# Main.net
KiCad netlist of a schematic drawn in Altium Designer
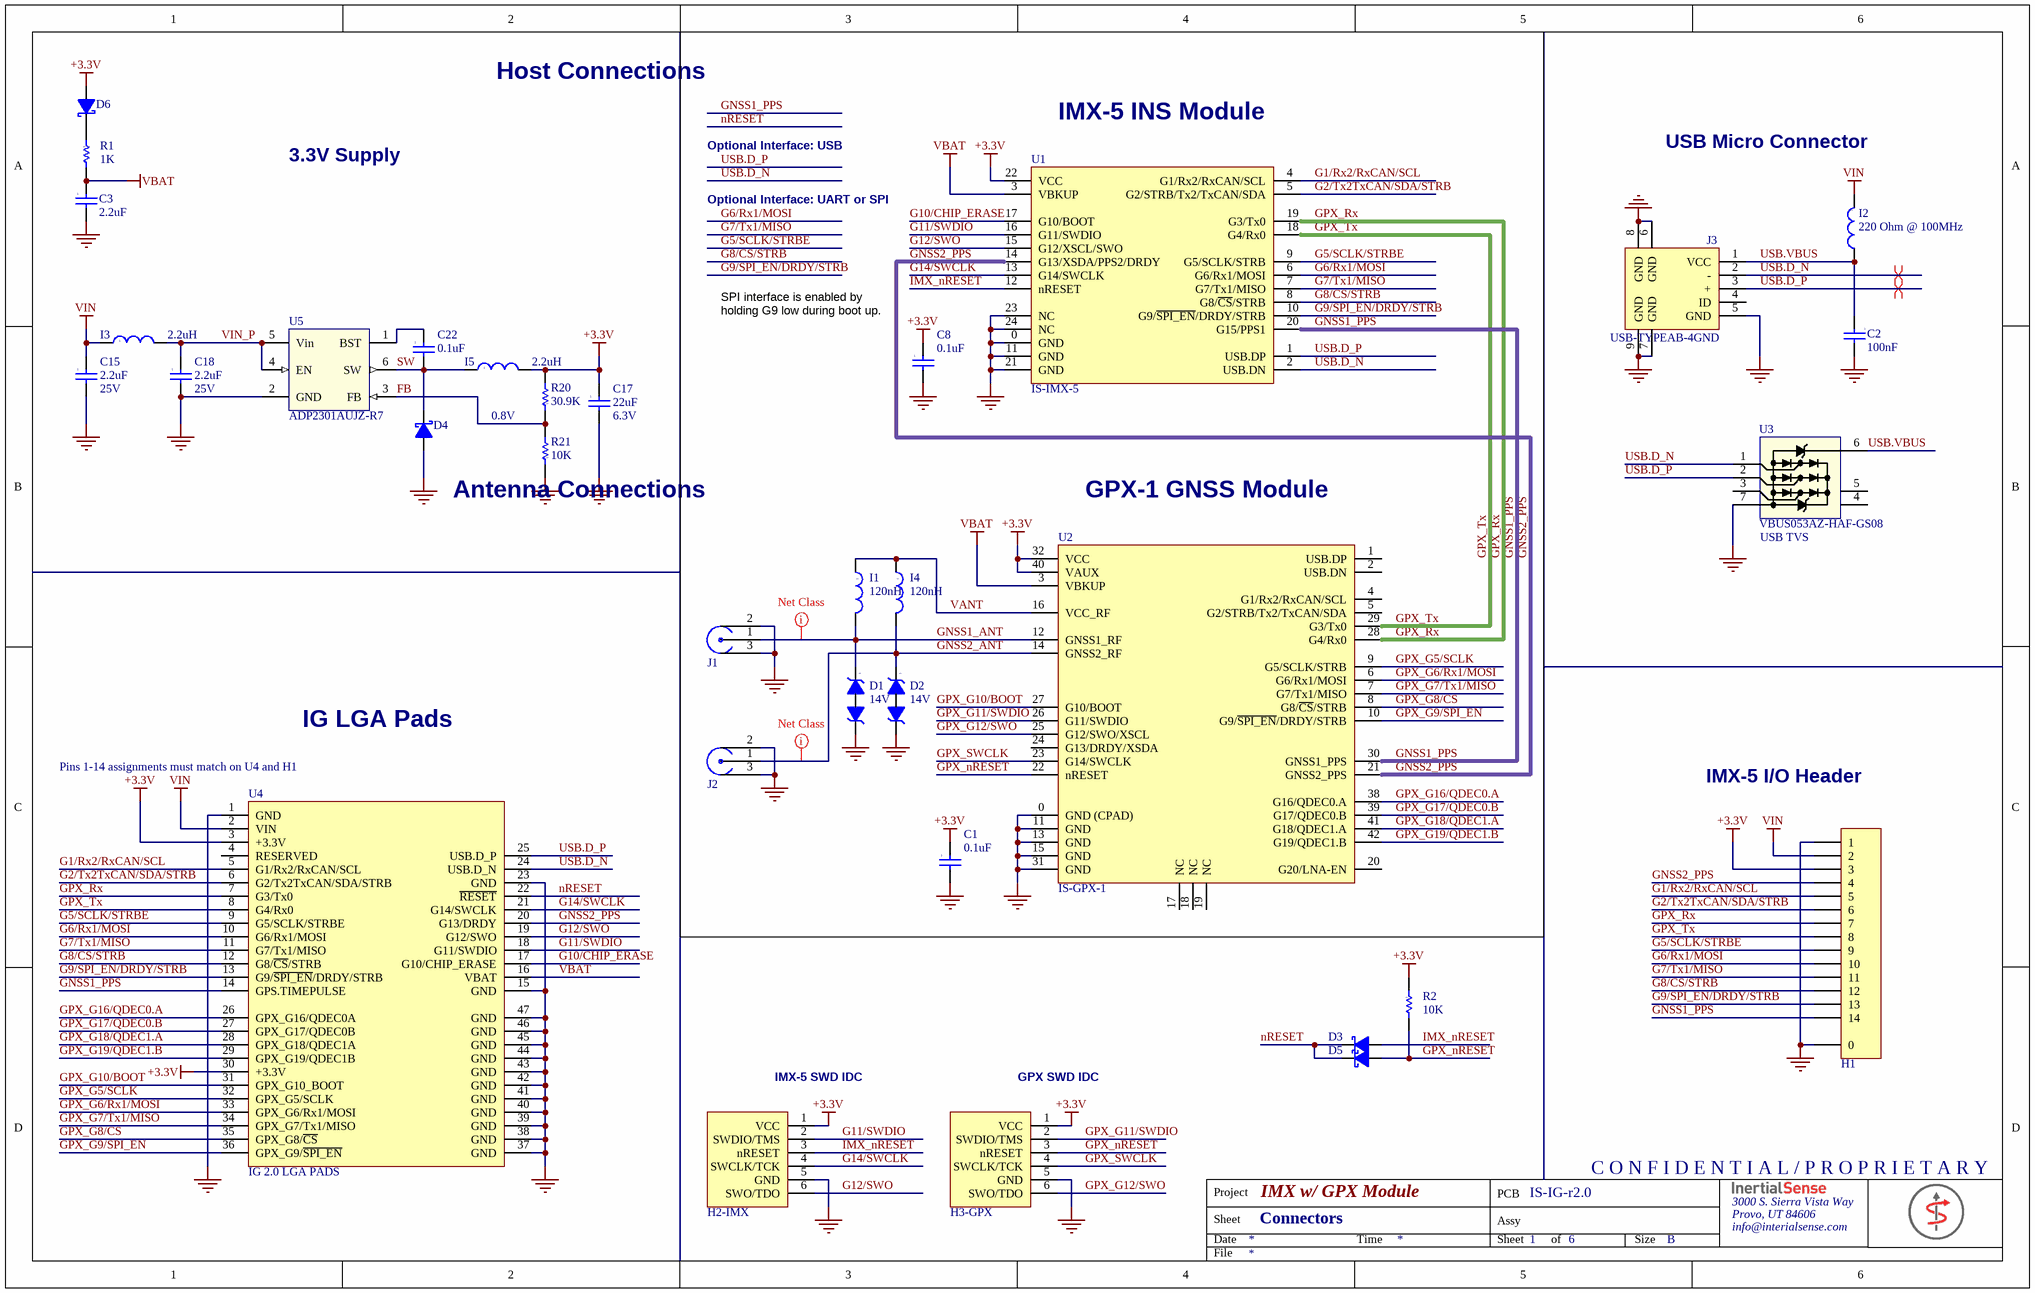
[diagram p0: Main.SchDoc]

(export (version "E")
  (design (tool "Eeschema 10.0.6"))
  (components
    (comp (ref "C1")
      (value "0.1uF")
      (footprint "0402")
      (description "CAP CER .10UF 50V X7R 10% 0402")
      (fields
        (field (name "MANUFACTURER") "TDK Corporation")
        (field (name "MANUFACTURER PART NUMBER") "C1005X7R1H104K")
        (field (name "PUBLISHER") "Altium Limited")
      )
      (libsource (lib "General") (part "Cap"))
    )
    (comp (ref "C2")
      (value "100nF")
      (footprint "0402")
      (description "CAP CER .10UF 50V X7R 10% 0402")
      (fields
        (field (name "MANUFACTURER") "TDK Corporation")
        (field (name "MANUFACTURER PART NUMBER") "C1005X7R1H104K")
        (field (name "PUBLISHER") "Altium Limited")
      )
      (libsource (lib "General") (part "Cap"))
    )
    (comp (ref "C3")
      (value "2.2uF")
      (footprint "0402")
      (description "0402 2.2 uF 6.3 V ±10% Tolerance X6S Multilayer Ceramic Capacitor")
      (fields
        (field (name "MANUFACTURER") "Murata")
        (field (name "MANUFACTURER PART NUMBER") "GRM155C80J225KE95D")
        (field (name "PUBLISHER") "Altium Limited")
      )
      (libsource (lib "General") (part "Cap"))
    )
    (comp (ref "C8")
      (value "0.1uF")
      (footprint "0402")
      (description "CAP CER .10UF 50V X7R 10% 0402")
      (fields
        (field (name "MANUFACTURER") "TDK Corporation")
        (field (name "MANUFACTURER PART NUMBER") "C1005X7R1H104K")
        (field (name "PUBLISHER") "Altium Limited")
      )
      (libsource (lib "General") (part "Cap"))
    )
    (comp (ref "C15")
      (value "2.2uF")
      (footprint "0603")
      (description "CAP CER 2.2UF 25V X6S 0603")
      (fields
        (field (name "MANUFACTURER") "Murata")
        (field (name "MANUFACTURER PART NUMBER") "GRT188C81E225KE13D")
        (field (name "VOLTAGE RATING") "25V")
        (field (name "PUBLISHER") "Altium Limited")
      )
      (libsource (lib "General") (part "Cap"))
    )
    (comp (ref "C17")
      (value "22uF")
      (footprint "0603")
      (description "CAP CER 22UF 6.3V X6S 0603")
      (fields
        (field (name "MANUFACTURER") "Murata")
        (field (name "MANUFACTURER PART NUMBER") "GRM188C80J226ME15D")
        (field (name "VOLTAGE RATING") "6.3V")
        (field (name "PUBLISHER") "Altium Limited")
      )
      (libsource (lib "General") (part "Cap"))
    )
    (comp (ref "C18")
      (value "2.2uF")
      (footprint "0603")
      (description "CAP CER 2.2UF 25V X6S 0603")
      (fields
        (field (name "MANUFACTURER") "Murata")
        (field (name "MANUFACTURER PART NUMBER") "GRT188C81E225KE13D")
        (field (name "VOLTAGE RATING") "25V")
        (field (name "PUBLISHER") "Altium Limited")
      )
      (libsource (lib "General") (part "Cap"))
    )
    (comp (ref "C22")
      (value "0.1uF")
      (footprint "0402")
      (description "CAP CER 0.1UF 50V X7R 0402")
      (fields
        (field (name "MANUFACTURER") "TDK")
        (field (name "MANUFACTURER PART NUMBER") "CGA2B3X7R1H104K050BB")
        (field (name "PUBLISHER") "Altium Limited")
      )
      (libsource (lib "General") (part "Cap"))
    )
    (comp (ref "D1")
      (value "Diode - Bidirectional Zener")
      (footprint "R0402")
      (description "LITTELFUSE - PESD0402-140 - DIODE, ESD PROTECTION, 0402, FULL REEL")
      (fields
        (field (name "MANUFACTURER") "Littelfuse")
        (field (name "MANUFACTURER PART NUMBER") "PESD0402-140")
        (field (name "WORKING VOLTAGE") "14V")
      )
      (libsource (lib "General") (part "Diode - Bidirectional Zener"))
    )
    (comp (ref "D2")
      (value "Diode - Bidirectional Zener")
      (footprint "R0402")
      (description "LITTELFUSE - PESD0402-140 - DIODE, ESD PROTECTION, 0402, FULL REEL")
      (fields
        (field (name "MANUFACTURER") "Littelfuse")
        (field (name "MANUFACTURER PART NUMBER") "PESD0402-140")
        (field (name "WORKING VOLTAGE") "14V")
      )
      (libsource (lib "General") (part "Diode - Bidirectional Zener"))
    )
    (comp (ref "D3")
      (value "Diode - Schottky")
      (footprint "D0402")
      (description "CDBQR0130L; SMT Schottky Diode; 35V 100mA; 2-Pin SOD-923F (0402)")
      (fields (field (name "MANUFACTURER") "Comchip") (field (name "MANUFACTURER PART NUMBER") "CDBQR0130L"))
      (libsource (lib "General") (part "Diode - Schottky"))
    )
    (comp (ref "D4")
      (value "Diode - Schottky")
      (footprint "D0603B")
      (description "DIODE SCHOTTKY 30V 2A 0603")
      (fields
        (field (name "MANUFACTURER") "Vishay")
        (field (name "MANUFACTURER PART NUMBER") "VSKY20301608-G4-08")
      )
      (libsource (lib "General") (part "Diode - Schottky"))
    )
    (comp (ref "D5")
      (value "Diode - Schottky")
      (footprint "D0402")
      (description "CDBQR0130L; SMT Schottky Diode; 35V 100mA; 2-Pin SOD-923F (0402)")
      (fields (field (name "MANUFACTURER") "Comchip") (field (name "MANUFACTURER PART NUMBER") "CDBQR0130L"))
      (libsource (lib "General") (part "Diode - Schottky"))
    )
    (comp (ref "D6")
      (value "Diode - Schottky")
      (footprint "D0603B")
      (description "DIODE SCHOTTKY 30V 2A 0603")
      (fields
        (field (name "MANUFACTURER") "Vishay")
        (field (name "MANUFACTURER PART NUMBER") "VSKY20301608-G4-08")
      )
      (libsource (lib "General") (part "Diode - Schottky"))
    )
    (comp (ref "H1")
      (value "Hdr - 14pin - mount")
      (footprint "SM14B-GHS-TB(LF)(SN)")
      (description "Conn Shrouded Header HDR 14 POS 1.25mm Solder ST Top Entry SMD T/R")
      (fields
        (field (name "MANUFACTURER") "JST")
        (field (name "MANUFACTURER PART NUMBER") "SM14B-GHS-TB(LF)(SN)")
      )
      (libsource (lib "Connectors") (part "Hdr - 14pin - mount"))
    )
    (comp (ref "H2-IMX")
      (value "TC2030-IDC")
      (footprint "TC2030-IDC-NL")
      (description "6 pin header")
      (libsource (lib "Connectors") (part "TC2030-IDC"))
    )
    (comp (ref "H3-GPX")
      (value "TC2030-IDC")
      (footprint "TC2030-IDC-NL")
      (description "6 pin header")
      (libsource (lib "Connectors") (part "TC2030-IDC"))
    )
    (comp (ref "I1")
      (value "120nH")
      (footprint "0402")
      (description "Inductor RF Chip Wirewound 120nH 5% 100MHz 20Q-Factor 110mA 2.66Ohm DCR 0402 Paper T/R")
      (fields
        (field (name "MANUFACTURER") "Murata")
        (field (name "MANUFACTURER PART NUMBER") "LQW15ANR12J00D")
      )
      (libsource (lib "") (part "Inductor_1"))
    )
    (comp (ref "I2")
      (value "220 Ohm @ 100MHz")
      (footprint "I0603")
      (description "FERRITE CHIP 220 OHM 2500MA 0603")
      (fields
        (field (name "MANUFACTURER") "Murata Electronics North America")
        (field (name "MANUFACTURER PART NUMBER") "BLM18SG221TN1D")
      )
      (libsource (lib "General") (part "Inductor"))
    )
    (comp (ref "I3")
      (value "2.2uH")
      (footprint "0806")
      (description "FIXED IND 2.2UH 1.2A 110 MOHM")
      (fields
        (field (name "MANUFACTURER") "TDK")
        (field (name "MANUFACTURER PART NUMBER") "MLP2016H2R2MT0S1")
      )
      (libsource (lib "") (part "Inductor_1"))
    )
    (comp (ref "I4")
      (value "120nH")
      (footprint "0402")
      (description "Inductor RF Chip Wirewound 120nH 5% 100MHz 20Q-Factor 110mA 2.66Ohm DCR 0402 Paper T/R")
      (fields
        (field (name "MANUFACTURER") "Murata")
        (field (name "MANUFACTURER PART NUMBER") "LQW15ANR12J00D")
      )
      (libsource (lib "") (part "Inductor_1"))
    )
    (comp (ref "I5")
      (value "2.2uH")
      (footprint "0806")
      (description "FIXED IND 2.2UH 1.2A 110 MOHM")
      (fields
        (field (name "MANUFACTURER") "TDK")
        (field (name "MANUFACTURER PART NUMBER") "MLP2016H2R2MT0S1")
      )
      (libsource (lib "") (part "Inductor_1"))
    )
    (comp (ref "J1")
      (value "RF - GND x 2")
      (footprint "RF UMC SMD")
      (description "CONN UMC RCPT STR 50 OHM SMD")
      (fields
        (field (name "MANUFACTURER") "Emerson Network Power Connectivity Johnson")
        (field (name "MANUFACTURER PART NUMBER") "128-0711-201")
      )
      (libsource (lib "Connectors") (part "RF - GND x 2"))
    )
    (comp (ref "J2")
      (value "RF - GND x 2")
      (footprint "RF UMC SMD")
      (description "CONN UMC RCPT STR 50 OHM SMD")
      (fields
        (field (name "MANUFACTURER") "Emerson Network Power Connectivity Johnson")
        (field (name "MANUFACTURER PART NUMBER") "128-0711-201")
      )
      (libsource (lib "Connectors") (part "RF - GND x 2"))
    )
    (comp (ref "J3")
      (value "USB-TYPEAB-4GND")
      (footprint "USB Micro AB R/A THR")
      (description "CONN USB AB 4POS")
      (fields
        (field (name "MANUFACTURER") "Amphenol FCI")
        (field (name "MANUFACTURER PART NUMBER") "10118194-0001LF")
      )
      (libsource (lib "Connectors") (part "USB-TYPEAB-4GND"))
    )
    (comp (ref "R1")
      (value "1K")
      (footprint "R0402")
      (description "1 kOhms ±1% 0.063W, 1/16W Chip Resistor 0402 (1005 Metric) Moisture Resistant Thick Film")
      (fields
        (field (name "MANUFACTURER") "Yageo")
        (field (name "MANUFACTURER PART NUMBER") "RC0402FR-071KL")
      )
      (libsource (lib "General") (part "Res"))
    )
    (comp (ref "R2")
      (value "10K")
      (footprint "R0402")
      (description "10 kOhms 1% 0.063W, 1/16W Chip Resistor 0402 (1005 Metric) Moisture Resistant Thick Film")
      (fields
        (field (name "MANUFACTURER") "Stackpole Electronics")
        (field (name "MANUFACTURER PART NUMBER") "RMCF0402FT10K0")
      )
      (libsource (lib "General") (part "Res"))
    )
    (comp (ref "R20")
      (value "30.9K")
      (footprint "R0402")
      (description "RES TF 30.9K OHM 1% 1/16W 0402")
      (fields
        (field (name "MANUFACTURER") "Stackpole Electronics Inc")
        (field (name "MANUFACTURER PART NUMBER") "RMCF0402FT30K9")
      )
      (libsource (lib "General") (part "Res"))
    )
    (comp (ref "R21")
      (value "10K")
      (footprint "R0402")
      (description "RES 10.0K OHM 1/16W 1% 0402 SMD")
      (fields
        (field (name "MANUFACTURER") "Yageo")
        (field (name "MANUFACTURER PART NUMBER") "RC0402FR-0710KL")
      )
      (libsource (lib "General") (part "Res"))
    )
    (comp (ref "U1")
      (value "IMX")
      (footprint "IS-IMX-5.0")
      (description "Inertial Sense IMX")
      (fields
        (field (name "MANUFACTURER") "Inertial Sense")
        (field (name "MANUFACTURER PART NUMBER") "IS-IMX-5")
      )
      (libsource (lib "IS-IMX-5") (part "IS-IMX-5.0"))
    )
    (comp (ref "U2")
      (value "GPX")
      (footprint "IS-GPX-1.0")
      (description "Inertial Sense GPX")
      (fields
        (field (name "MANUFACTURER") "Inertial Sense")
        (field (name "MANUFACTURER PART NUMBER") "IS-GPX-1")
      )
      (libsource (lib "IS-GPX-1") (part "IS-GPX-1.0"))
    )
    (comp (ref "U3")
      (value "VBUS053")
      (footprint "QFN50P160X160X60-6N")
      (description "ESD SUPPRESS 5.5V 36W 3-Line USB")
      (fields
        (field (name "MANUFACTURER") "Vishay Semiconductors")
        (field (name "MANUFACTURER PART NUMBER") "VBUS053AZ-HAF-GS08")
      )
      (libsource (lib "ICs") (part "VBUS053"))
    )
    (comp (ref "U4")
      (value "IG 2.0 LGA PADS")
      (footprint "IG-2.0_LGA")
      (description "IMX multi-frequency RTK-GNSS Module")
      (libsource (lib "Sensors") (part "IG_2.0_LGA"))
    )
    (comp (ref "U5")
      (value "ADP2301")
      (footprint "MO-178-AB")
      (description "IC BUCK ADJ 1.2A 6TSOT")
      (fields
        (field (name "MANUFACTURER") "Analog Devices Inc")
        (field (name "MANUFACTURER PART NUMBER") "ADP2301AUJZ-R7")
      )
      (libsource (lib "ICs") (part "ADP2301"))
    )
  )
  (nets
    (net (code "1") (name "+3.3V") (class "Default")
      (node (ref "C1") (pin "1") (pinfunction "1_1") (pintype "passive"))
      (node (ref "C17") (pin "1") (pinfunction "1_1") (pintype "passive"))
      (node (ref "C8") (pin "1") (pinfunction "1_1") (pintype "passive"))
      (node (ref "D6") (pin "A") (pinfunction "A_A") (pintype "passive"))
      (node (ref "H1") (pin "3") (pinfunction "3_3") (pintype "passive"))
      (node (ref "H2-IMX") (pin "1") (pinfunction "VCC_1") (pintype "passive"))
      (node (ref "H3-GPX") (pin "1") (pinfunction "VCC_1") (pintype "passive"))
      (node (ref "I5") (pin "2") (pinfunction "2_2") (pintype "passive"))
      (node (ref "R2") (pin "1") (pinfunction "1_1") (pintype "passive"))
      (node (ref "R20") (pin "2") (pinfunction "2_2") (pintype "passive"))
      (node (ref "U1") (pin "22") (pinfunction "VCC_22") (pintype "power_in"))
      (node (ref "U2") (pin "32") (pinfunction "VCC_32") (pintype "power_in"))
      (node (ref "U2") (pin "40") (pinfunction "VAUX_40") (pintype "power_in"))
      (node (ref "U4") (pin "3") (pinfunction "+3.3V_3") (pintype "passive"))
      (node (ref "U4") (pin "30") (pinfunction "+3.3V_30") (pintype "passive"))
    )
    (net (code "2") (name "/FB") (class "Default")
      (node (ref "R20") (pin "1") (pinfunction "1_1") (pintype "passive"))
      (node (ref "R21") (pin "2") (pinfunction "2_2") (pintype "passive"))
      (node (ref "U5") (pin "3") (pinfunction "FB_3") (pintype "input"))
    )
    (net (code "3") (name "/G1{slash}Rx2{slash}RxCAN{slash}SCL") (class "Default")
      (node (ref "H1") (pin "5") (pinfunction "5_5") (pintype "passive"))
      (node (ref "U1") (pin "4") (pinfunction "G1/Rx2/RxCAN/SCL_4") (pintype "passive"))
      (node (ref "U4") (pin "5") (pinfunction "G1/Rx2/RxCAN/SCL_5") (pintype "passive"))
    )
    (net (code "4") (name "/G2{slash}Tx2TxCAN{slash}SDA{slash}STRB") (class "Default")
      (node (ref "H1") (pin "6") (pinfunction "6_6") (pintype "passive"))
      (node (ref "U1") (pin "5") (pinfunction "G2/STRB/Tx2/TxCAN/SDA_5") (pintype "passive"))
      (node (ref "U4") (pin "6") (pinfunction "G2/Tx2TxCAN/SDA/STRB_6") (pintype "passive"))
    )
    (net (code "5") (name "/G5{slash}SCLK{slash}STRBE") (class "Default")
      (node (ref "H1") (pin "9") (pinfunction "9_9") (pintype "passive"))
      (node (ref "U1") (pin "9") (pinfunction "G5/SCLK/STRB_9") (pintype "passive"))
      (node (ref "U4") (pin "9") (pinfunction "G5/SCLK/STRBE_9") (pintype "passive"))
    )
    (net (code "6") (name "/G6{slash}Rx1{slash}MOSI") (class "Default")
      (node (ref "H1") (pin "10") (pinfunction "10_10") (pintype "passive"))
      (node (ref "U1") (pin "6") (pinfunction "G6/Rx1/MOSI_6") (pintype "passive"))
      (node (ref "U4") (pin "10") (pinfunction "G6/Rx1/MOSI_10") (pintype "passive"))
    )
    (net (code "7") (name "/G7{slash}Tx1{slash}MISO") (class "Default")
      (node (ref "H1") (pin "11") (pinfunction "11_11") (pintype "passive"))
      (node (ref "U1") (pin "7") (pinfunction "G7/Tx1/MISO_7") (pintype "passive"))
      (node (ref "U4") (pin "11") (pinfunction "G7/Tx1/MISO_11") (pintype "passive"))
    )
    (net (code "8") (name "/G8{slash}~{CS}{slash}STRB") (class "Default")
      (node (ref "H1") (pin "12") (pinfunction "12_12") (pintype "passive"))
      (node (ref "U1") (pin "8") (pinfunction "G8/~{CS}/STRB_8") (pintype "passive"))
      (node (ref "U4") (pin "12") (pinfunction "G8/~{CS}/STRB_12") (pintype "passive"))
    )
    (net (code "9") (name "/G9{slash}~{SPI_EN}{slash}DRDY{slash}STRB") (class "Default")
      (node (ref "H1") (pin "13") (pinfunction "13_13") (pintype "passive"))
      (node (ref "U1") (pin "10") (pinfunction "G9/~{SPI_EN}/DRDY/STRB_10") (pintype "passive"))
      (node (ref "U4") (pin "13") (pinfunction "G9/~{SPI_EN}/DRDY/STRB_13") (pintype "passive"))
    )
    (net (code "10") (name "/G10{slash}CHIP_ERASE") (class "Default")
      (node (ref "U1") (pin "17") (pinfunction "G10/BOOT_17") (pintype "passive"))
      (node (ref "U4") (pin "17") (pinfunction "G10/CHIP_ERASE_17") (pintype "passive"))
    )
    (net (code "11") (name "/G11{slash}SWDIO") (class "Default")
      (node (ref "H2-IMX") (pin "2") (pinfunction "SWDIO/TMS_2") (pintype "passive"))
      (node (ref "U1") (pin "16") (pinfunction "G11/SWDIO_16") (pintype "passive"))
      (node (ref "U4") (pin "18") (pinfunction "G11/SWDIO_18") (pintype "passive"))
    )
    (net (code "12") (name "/G12{slash}SWO") (class "Default")
      (node (ref "H2-IMX") (pin "6") (pinfunction "SWO/TDO_6") (pintype "passive"))
      (node (ref "U1") (pin "15") (pinfunction "G12/XSCL/SWO_15") (pintype "passive"))
      (node (ref "U4") (pin "19") (pinfunction "G12/SWO_19") (pintype "passive"))
    )
    (net (code "13") (name "/G14{slash}SWCLK") (class "Default")
      (node (ref "H2-IMX") (pin "4") (pinfunction "SWCLK/TCK_4") (pintype "passive"))
      (node (ref "U1") (pin "13") (pinfunction "G14/SWCLK_13") (pintype "passive"))
      (node (ref "U4") (pin "21") (pinfunction "G14/SWCLK_21") (pintype "passive"))
    )
    (net (code "14") (name "/GNSS1_ANT") (class "Default")
      (node (ref "D1") (pin "1") (pinfunction "1_1") (pintype "passive"))
      (node (ref "I1") (pin "2") (pinfunction "2_2") (pintype "passive"))
      (node (ref "J1") (pin "1") (pinfunction "1_1") (pintype "passive"))
      (node (ref "U2") (pin "12") (pinfunction "GNSS1_RF_12") (pintype "passive"))
    )
    (net (code "15") (name "/GNSS1_PPS") (class "Default")
      (node (ref "H1") (pin "14") (pinfunction "14_14") (pintype "passive"))
      (node (ref "U1") (pin "20") (pinfunction "G15/PPS1_20") (pintype "passive"))
      (node (ref "U2") (pin "30") (pinfunction "GNSS1_PPS_30") (pintype "passive"))
      (node (ref "U4") (pin "14") (pinfunction "GPS.TIMEPULSE_14") (pintype "passive"))
    )
    (net (code "16") (name "/GNSS2_ANT") (class "Default")
      (node (ref "D2") (pin "1") (pinfunction "1_1") (pintype "passive"))
      (node (ref "I4") (pin "2") (pinfunction "2_2") (pintype "passive"))
      (node (ref "J2") (pin "1") (pinfunction "1_1") (pintype "passive"))
      (node (ref "U2") (pin "14") (pinfunction "GNSS2_RF_14") (pintype "passive"))
    )
    (net (code "17") (name "/GNSS2_PPS") (class "Default")
      (node (ref "H1") (pin "4") (pinfunction "4_4") (pintype "passive"))
      (node (ref "U1") (pin "14") (pinfunction "G13/XSDA/PPS2/DRDY_14") (pintype "passive"))
      (node (ref "U2") (pin "21") (pinfunction "GNSS2_PPS_21") (pintype "passive"))
      (node (ref "U4") (pin "20") (pinfunction "G13/DRDY_20") (pintype "passive"))
    )
    (net (code "18") (name "/GPX_G5{slash}SCLK") (class "Default")
      (node (ref "U2") (pin "9") (pinfunction "G5/SCLK/STRB_9") (pintype "passive"))
      (node (ref "U4") (pin "32") (pinfunction "GPX_G5/SCLK_32") (pintype "passive"))
    )
    (net (code "19") (name "/GPX_G6{slash}Rx1{slash}MOSI") (class "Default")
      (node (ref "U2") (pin "6") (pinfunction "G6/Rx1/MOSI_6") (pintype "passive"))
      (node (ref "U4") (pin "33") (pinfunction "GPX_G6/Rx1/MOSI_33") (pintype "passive"))
    )
    (net (code "20") (name "/GPX_G7{slash}Tx1{slash}MISO") (class "Default")
      (node (ref "U2") (pin "7") (pinfunction "G7/Tx1/MISO_7") (pintype "passive"))
      (node (ref "U4") (pin "34") (pinfunction "GPX_G7/Tx1/MISO_34") (pintype "passive"))
    )
    (net (code "21") (name "/GPX_G8{slash}~{CS}") (class "Default")
      (node (ref "U2") (pin "8") (pinfunction "G8/~{CS}/STRB_8") (pintype "passive"))
      (node (ref "U4") (pin "35") (pinfunction "GPX_G8/~{CS}_35") (pintype "passive"))
    )
    (net (code "22") (name "/GPX_G9{slash}~{SPI_EN}") (class "Default")
      (node (ref "U2") (pin "10") (pinfunction "G9/~{SPI_EN}/DRDY/STRB_10") (pintype "passive"))
      (node (ref "U4") (pin "36") (pinfunction "GPX_G9/~{SPI_EN}_36") (pintype "passive"))
    )
    (net (code "23") (name "/GPX_G10{slash}BOOT") (class "Default")
      (node (ref "U2") (pin "27") (pinfunction "G10/BOOT_27") (pintype "passive"))
      (node (ref "U4") (pin "31") (pinfunction "GPX_G10_BOOT_31") (pintype "passive"))
    )
    (net (code "24") (name "/GPX_G11{slash}SWDIO") (class "Default")
      (node (ref "H3-GPX") (pin "2") (pinfunction "SWDIO/TMS_2") (pintype "passive"))
      (node (ref "U2") (pin "26") (pinfunction "G11/SWDIO_26") (pintype "passive"))
    )
    (net (code "25") (name "/GPX_G12{slash}SWO") (class "Default")
      (node (ref "H3-GPX") (pin "6") (pinfunction "SWO/TDO_6") (pintype "passive"))
      (node (ref "U2") (pin "25") (pinfunction "G12/SWO/XSCL_25") (pintype "passive"))
    )
    (net (code "26") (name "/GPX_G16{slash}QDEC0.A") (class "Default")
      (node (ref "U2") (pin "38") (pinfunction "G16/QDEC0.A_38") (pintype "passive"))
      (node (ref "U4") (pin "26") (pinfunction "GPX_G16/QDEC0A_26") (pintype "passive"))
    )
    (net (code "27") (name "/GPX_G17{slash}QDEC0.B") (class "Default")
      (node (ref "U2") (pin "39") (pinfunction "G17/QDEC0.B_39") (pintype "passive"))
      (node (ref "U4") (pin "27") (pinfunction "GPX_G17/QDEC0B_27") (pintype "passive"))
    )
    (net (code "28") (name "/GPX_G18{slash}QDEC1.A") (class "Default")
      (node (ref "U2") (pin "41") (pinfunction "G18/QDEC1.A_41") (pintype "passive"))
      (node (ref "U4") (pin "28") (pinfunction "GPX_G18/QDEC1A_28") (pintype "passive"))
    )
    (net (code "29") (name "/GPX_G19{slash}QDEC1.B") (class "Default")
      (node (ref "U2") (pin "42") (pinfunction "G19/QDEC1.B_42") (pintype "passive"))
      (node (ref "U4") (pin "29") (pinfunction "GPX_G19/QDEC1B_29") (pintype "passive"))
    )
    (net (code "30") (name "/GPX_Rx") (class "Default")
      (node (ref "H1") (pin "7") (pinfunction "7_7") (pintype "passive"))
      (node (ref "U1") (pin "19") (pinfunction "G3/Tx0_19") (pintype "passive"))
      (node (ref "U2") (pin "28") (pinfunction "G4/Rx0_28") (pintype "passive"))
      (node (ref "U4") (pin "7") (pinfunction "G3/Tx0_7") (pintype "passive"))
    )
    (net (code "31") (name "/GPX_SWCLK") (class "Default")
      (node (ref "H3-GPX") (pin "4") (pinfunction "SWCLK/TCK_4") (pintype "passive"))
      (node (ref "U2") (pin "23") (pinfunction "G14/SWCLK_23") (pintype "passive"))
    )
    (net (code "32") (name "/GPX_Tx") (class "Default")
      (node (ref "H1") (pin "8") (pinfunction "8_8") (pintype "passive"))
      (node (ref "U1") (pin "18") (pinfunction "G4/Rx0_18") (pintype "passive"))
      (node (ref "U2") (pin "29") (pinfunction "G3/Tx0_29") (pintype "passive"))
      (node (ref "U4") (pin "8") (pinfunction "G4/Rx0_8") (pintype "passive"))
    )
    (net (code "33") (name "/GPX_nRESET") (class "Default")
      (node (ref "D5") (pin "A") (pinfunction "A_A") (pintype "passive"))
      (node (ref "H3-GPX") (pin "3") (pinfunction "nRESET_3") (pintype "passive"))
      (node (ref "R2") (pin "2") (pinfunction "2_2") (pintype "passive"))
      (node (ref "U2") (pin "22") (pinfunction "nRESET_22") (pintype "passive"))
    )
    (net (code "34") (name "/IMX_nRESET") (class "Default")
      (node (ref "D3") (pin "A") (pinfunction "A_A") (pintype "passive"))
      (node (ref "H2-IMX") (pin "3") (pinfunction "nRESET_3") (pintype "passive"))
      (node (ref "U1") (pin "12") (pinfunction "nRESET_12") (pintype "passive"))
    )
    (net (code "35") (name "/SW") (class "Default")
      (node (ref "C22") (pin "2") (pinfunction "2_2") (pintype "passive"))
      (node (ref "D4") (pin "C") (pinfunction "C_C") (pintype "passive"))
      (node (ref "I5") (pin "1") (pinfunction "1_1") (pintype "passive"))
      (node (ref "U5") (pin "6") (pinfunction "SW_6") (pintype "output"))
    )
    (net (code "36") (name "/USB.D_N") (class "Default")
      (node (ref "J3") (pin "2") (pinfunction "-_2") (pintype "passive"))
      (node (ref "U1") (pin "2") (pinfunction "USB.DN_2") (pintype "passive"))
      (node (ref "U3") (pin "1") (pintype "passive"))
      (node (ref "U4") (pin "24") (pinfunction "USB.D_N_24") (pintype "passive"))
    )
    (net (code "37") (name "/USB.D_P") (class "Default")
      (node (ref "J3") (pin "3") (pinfunction "+_3") (pintype "passive"))
      (node (ref "U1") (pin "1") (pinfunction "USB.DP_1") (pintype "passive"))
      (node (ref "U3") (pin "2") (pintype "passive"))
      (node (ref "U4") (pin "25") (pinfunction "USB.D_P_25") (pintype "passive"))
    )
    (net (code "38") (name "/USB.VBUS") (class "Default")
      (node (ref "C2") (pin "1") (pinfunction "1_1") (pintype "passive"))
      (node (ref "I2") (pin "2") (pinfunction "2_2") (pintype "passive"))
      (node (ref "J3") (pin "1") (pinfunction "VCC_1") (pintype "passive"))
      (node (ref "U3") (pin "6") (pintype "passive"))
    )
    (net (code "39") (name "/VANT") (class "Default")
      (node (ref "I1") (pin "1") (pinfunction "1_1") (pintype "passive"))
      (node (ref "I4") (pin "1") (pinfunction "1_1") (pintype "passive"))
      (node (ref "U2") (pin "16") (pinfunction "VCC_RF_16") (pintype "power_in"))
    )
    (net (code "40") (name "/VIN_P") (class "Default")
      (node (ref "C18") (pin "1") (pinfunction "1_1") (pintype "passive"))
      (node (ref "I3") (pin "2") (pinfunction "2_2") (pintype "passive"))
      (node (ref "U5") (pin "4") (pinfunction "EN_4") (pintype "input"))
      (node (ref "U5") (pin "5") (pinfunction "Vin_5") (pintype "power_in"))
    )
    (net (code "41") (name "/nRESET") (class "Default")
      (node (ref "D3") (pin "C") (pinfunction "C_C") (pintype "passive"))
      (node (ref "D5") (pin "C") (pinfunction "C_C") (pintype "passive"))
      (node (ref "U4") (pin "22") (pinfunction "~{RESET}_22") (pintype "passive"))
    )
    (net (code "42") (name "GND") (class "Default")
      (node (ref "C1") (pin "2") (pinfunction "2_2") (pintype "passive"))
      (node (ref "C15") (pin "2") (pinfunction "2_2") (pintype "passive"))
      (node (ref "C17") (pin "2") (pinfunction "2_2") (pintype "passive"))
      (node (ref "C18") (pin "2") (pinfunction "2_2") (pintype "passive"))
      (node (ref "C2") (pin "2") (pinfunction "2_2") (pintype "passive"))
      (node (ref "C3") (pin "2") (pinfunction "2_2") (pintype "passive"))
      (node (ref "C8") (pin "2") (pinfunction "2_2") (pintype "passive"))
      (node (ref "D1") (pin "2") (pinfunction "2_2") (pintype "passive"))
      (node (ref "D2") (pin "2") (pinfunction "2_2") (pintype "passive"))
      (node (ref "D4") (pin "A") (pinfunction "A_A") (pintype "passive"))
      (node (ref "H1") (pin "0") (pinfunction "0_0") (pintype "passive"))
      (node (ref "H1") (pin "1") (pinfunction "1_1") (pintype "passive"))
      (node (ref "H2-IMX") (pin "5") (pinfunction "GND_5") (pintype "passive"))
      (node (ref "H3-GPX") (pin "5") (pinfunction "GND_5") (pintype "passive"))
      (node (ref "J1") (pin "2") (pinfunction "2_2") (pintype "passive"))
      (node (ref "J1") (pin "3") (pinfunction "3_3") (pintype "passive"))
      (node (ref "J2") (pin "2") (pinfunction "2_2") (pintype "passive"))
      (node (ref "J2") (pin "3") (pinfunction "3_3") (pintype "passive"))
      (node (ref "J3") (pin "5") (pinfunction "GND_5") (pintype "passive"))
      (node (ref "J3") (pin "6") (pinfunction "GND_6") (pintype "passive"))
      (node (ref "J3") (pin "7") (pinfunction "GND_7") (pintype "passive"))
      (node (ref "J3") (pin "8") (pinfunction "GND_8") (pintype "passive"))
      (node (ref "J3") (pin "9") (pinfunction "GND_9") (pintype "passive"))
      (node (ref "R21") (pin "1") (pinfunction "1_1") (pintype "passive"))
      (node (ref "U1") (pin "0") (pinfunction "GND_0") (pintype "power_in"))
      (node (ref "U1") (pin "11") (pinfunction "GND_11") (pintype "power_in"))
      (node (ref "U1") (pin "21") (pinfunction "GND_21") (pintype "power_in"))
      (node (ref "U1") (pin "23") (pinfunction "NC_23") (pintype "power_in"))
      (node (ref "U1") (pin "24") (pinfunction "NC_24") (pintype "power_in"))
      (node (ref "U2") (pin "0") (pinfunction "GND_(CPAD)_0") (pintype "power_in"))
      (node (ref "U2") (pin "11") (pinfunction "GND_11") (pintype "power_in"))
      (node (ref "U2") (pin "13") (pinfunction "GND_13") (pintype "power_in"))
      (node (ref "U2") (pin "15") (pinfunction "GND_15") (pintype "power_in"))
      (node (ref "U2") (pin "31") (pinfunction "GND_31") (pintype "power_in"))
      (node (ref "U3") (pin "7") (pintype "passive"))
      (node (ref "U4") (pin "1") (pinfunction "GND_1") (pintype "passive"))
      (node (ref "U4") (pin "15") (pinfunction "GND_15") (pintype "passive"))
      (node (ref "U4") (pin "23") (pinfunction "GND_23") (pintype "passive"))
      (node (ref "U4") (pin "37") (pinfunction "GND_37") (pintype "passive"))
      (node (ref "U4") (pin "38") (pinfunction "GND_38") (pintype "passive"))
      (node (ref "U4") (pin "39") (pinfunction "GND_39") (pintype "passive"))
      (node (ref "U4") (pin "40") (pinfunction "GND_40") (pintype "passive"))
      (node (ref "U4") (pin "41") (pinfunction "GND_41") (pintype "passive"))
      (node (ref "U4") (pin "42") (pinfunction "GND_42") (pintype "passive"))
      (node (ref "U4") (pin "43") (pinfunction "GND_43") (pintype "passive"))
      (node (ref "U4") (pin "44") (pinfunction "GND_44") (pintype "passive"))
      (node (ref "U4") (pin "45") (pinfunction "GND_45") (pintype "passive"))
      (node (ref "U4") (pin "46") (pinfunction "GND_46") (pintype "passive"))
      (node (ref "U4") (pin "47") (pinfunction "GND_47") (pintype "passive"))
      (node (ref "U5") (pin "2") (pinfunction "GND_2") (pintype "power_in"))
    )
    (net (code "43") (name "Net-(D6-PadC)") (class "Default")
      (node (ref "D6") (pin "C") (pinfunction "C_C") (pintype "passive"))
      (node (ref "R1") (pin "1") (pinfunction "1_1") (pintype "passive"))
    )
    (net (code "44") (name "Net-(U5-BST)") (class "Default")
      (node (ref "C22") (pin "1") (pinfunction "1_1") (pintype "passive"))
      (node (ref "U5") (pin "1") (pinfunction "BST_1") (pintype "passive"))
    )
    (net (code "45") (name "VBAT") (class "Default")
      (node (ref "C3") (pin "1") (pinfunction "1_1") (pintype "passive"))
      (node (ref "R1") (pin "2") (pinfunction "2_2") (pintype "passive"))
      (node (ref "U1") (pin "3") (pinfunction "VBKUP_3") (pintype "passive"))
      (node (ref "U2") (pin "3") (pinfunction "VBKUP_3") (pintype "passive"))
      (node (ref "U4") (pin "16") (pinfunction "VBAT_16") (pintype "passive"))
    )
    (net (code "46") (name "VIN") (class "Default")
      (node (ref "C15") (pin "1") (pinfunction "1_1") (pintype "passive"))
      (node (ref "H1") (pin "2") (pinfunction "2_2") (pintype "passive"))
      (node (ref "I2") (pin "1") (pinfunction "1_1") (pintype "passive"))
      (node (ref "I3") (pin "1") (pinfunction "1_1") (pintype "passive"))
      (node (ref "U4") (pin "2") (pinfunction "VIN_2") (pintype "passive"))
    )
    (net (code "47") (name "unconnected-(J3-ID-Pad4)") (class "Default")
      (node (ref "J3") (pin "4") (pinfunction "ID_4") (pintype "passive"))
    )
    (net (code "48") (name "unconnected-(U2-G1{slash}Rx2{slash}RxCAN{slash}SCL-Pad4)") (class "Default")
      (node (ref "U2") (pin "4") (pinfunction "G1/Rx2/RxCAN/SCL_4") (pintype "passive"))
    )
    (net (code "49") (name "unconnected-(U2-G2{slash}STRB{slash}Tx2{slash}TxCAN{slash}SDA-Pad5)") (class "Default")
      (node (ref "U2") (pin "5") (pinfunction "G2/STRB/Tx2/TxCAN/SDA_5") (pintype "passive"))
    )
    (net (code "50") (name "unconnected-(U2-G13{slash}DRDY{slash}XSDA-Pad24)") (class "Default")
      (node (ref "U2") (pin "24") (pinfunction "G13/DRDY/XSDA_24") (pintype "passive"))
    )
    (net (code "51") (name "unconnected-(U2-G20{slash}LNA-EN-Pad20)") (class "Default")
      (node (ref "U2") (pin "20") (pinfunction "G20/LNA-EN_20") (pintype "passive"))
    )
    (net (code "52") (name "unconnected-(U2-NC-Pad17)") (class "Default")
      (node (ref "U2") (pin "17") (pinfunction "NC_17") (pintype "passive"))
    )
    (net (code "53") (name "unconnected-(U2-NC-Pad18)") (class "Default")
      (node (ref "U2") (pin "18") (pinfunction "NC_18") (pintype "passive"))
    )
    (net (code "54") (name "unconnected-(U2-NC-Pad19)") (class "Default")
      (node (ref "U2") (pin "19") (pinfunction "NC_19") (pintype "passive"))
    )
    (net (code "55") (name "unconnected-(U2-USB.DN-Pad2)") (class "Default")
      (node (ref "U2") (pin "2") (pinfunction "USB.DN_2") (pintype "passive"))
    )
    (net (code "56") (name "unconnected-(U2-USB.DP-Pad1)") (class "Default")
      (node (ref "U2") (pin "1") (pinfunction "USB.DP_1") (pintype "passive"))
    )
    (net (code "57") (name "unconnected-(U3-Pad3)") (class "Default")
      (node (ref "U3") (pin "3") (pintype "passive"))
    )
    (net (code "58") (name "unconnected-(U3-nc-Pad4)") (class "Default")
      (node (ref "U3") (pin "4") (pinfunction "nc_4") (pintype "passive"))
    )
    (net (code "59") (name "unconnected-(U3-nc-Pad5)") (class "Default")
      (node (ref "U3") (pin "5") (pinfunction "nc_5") (pintype "passive"))
    )
    (net (code "60") (name "unconnected-(U4-RESERVED-Pad4)") (class "Default")
      (node (ref "U4") (pin "4") (pinfunction "RESERVED_4") (pintype "passive"))
    )
  )
)
